# Diverter.net
KiCad netlist of a schematic drawn in Altium Designer
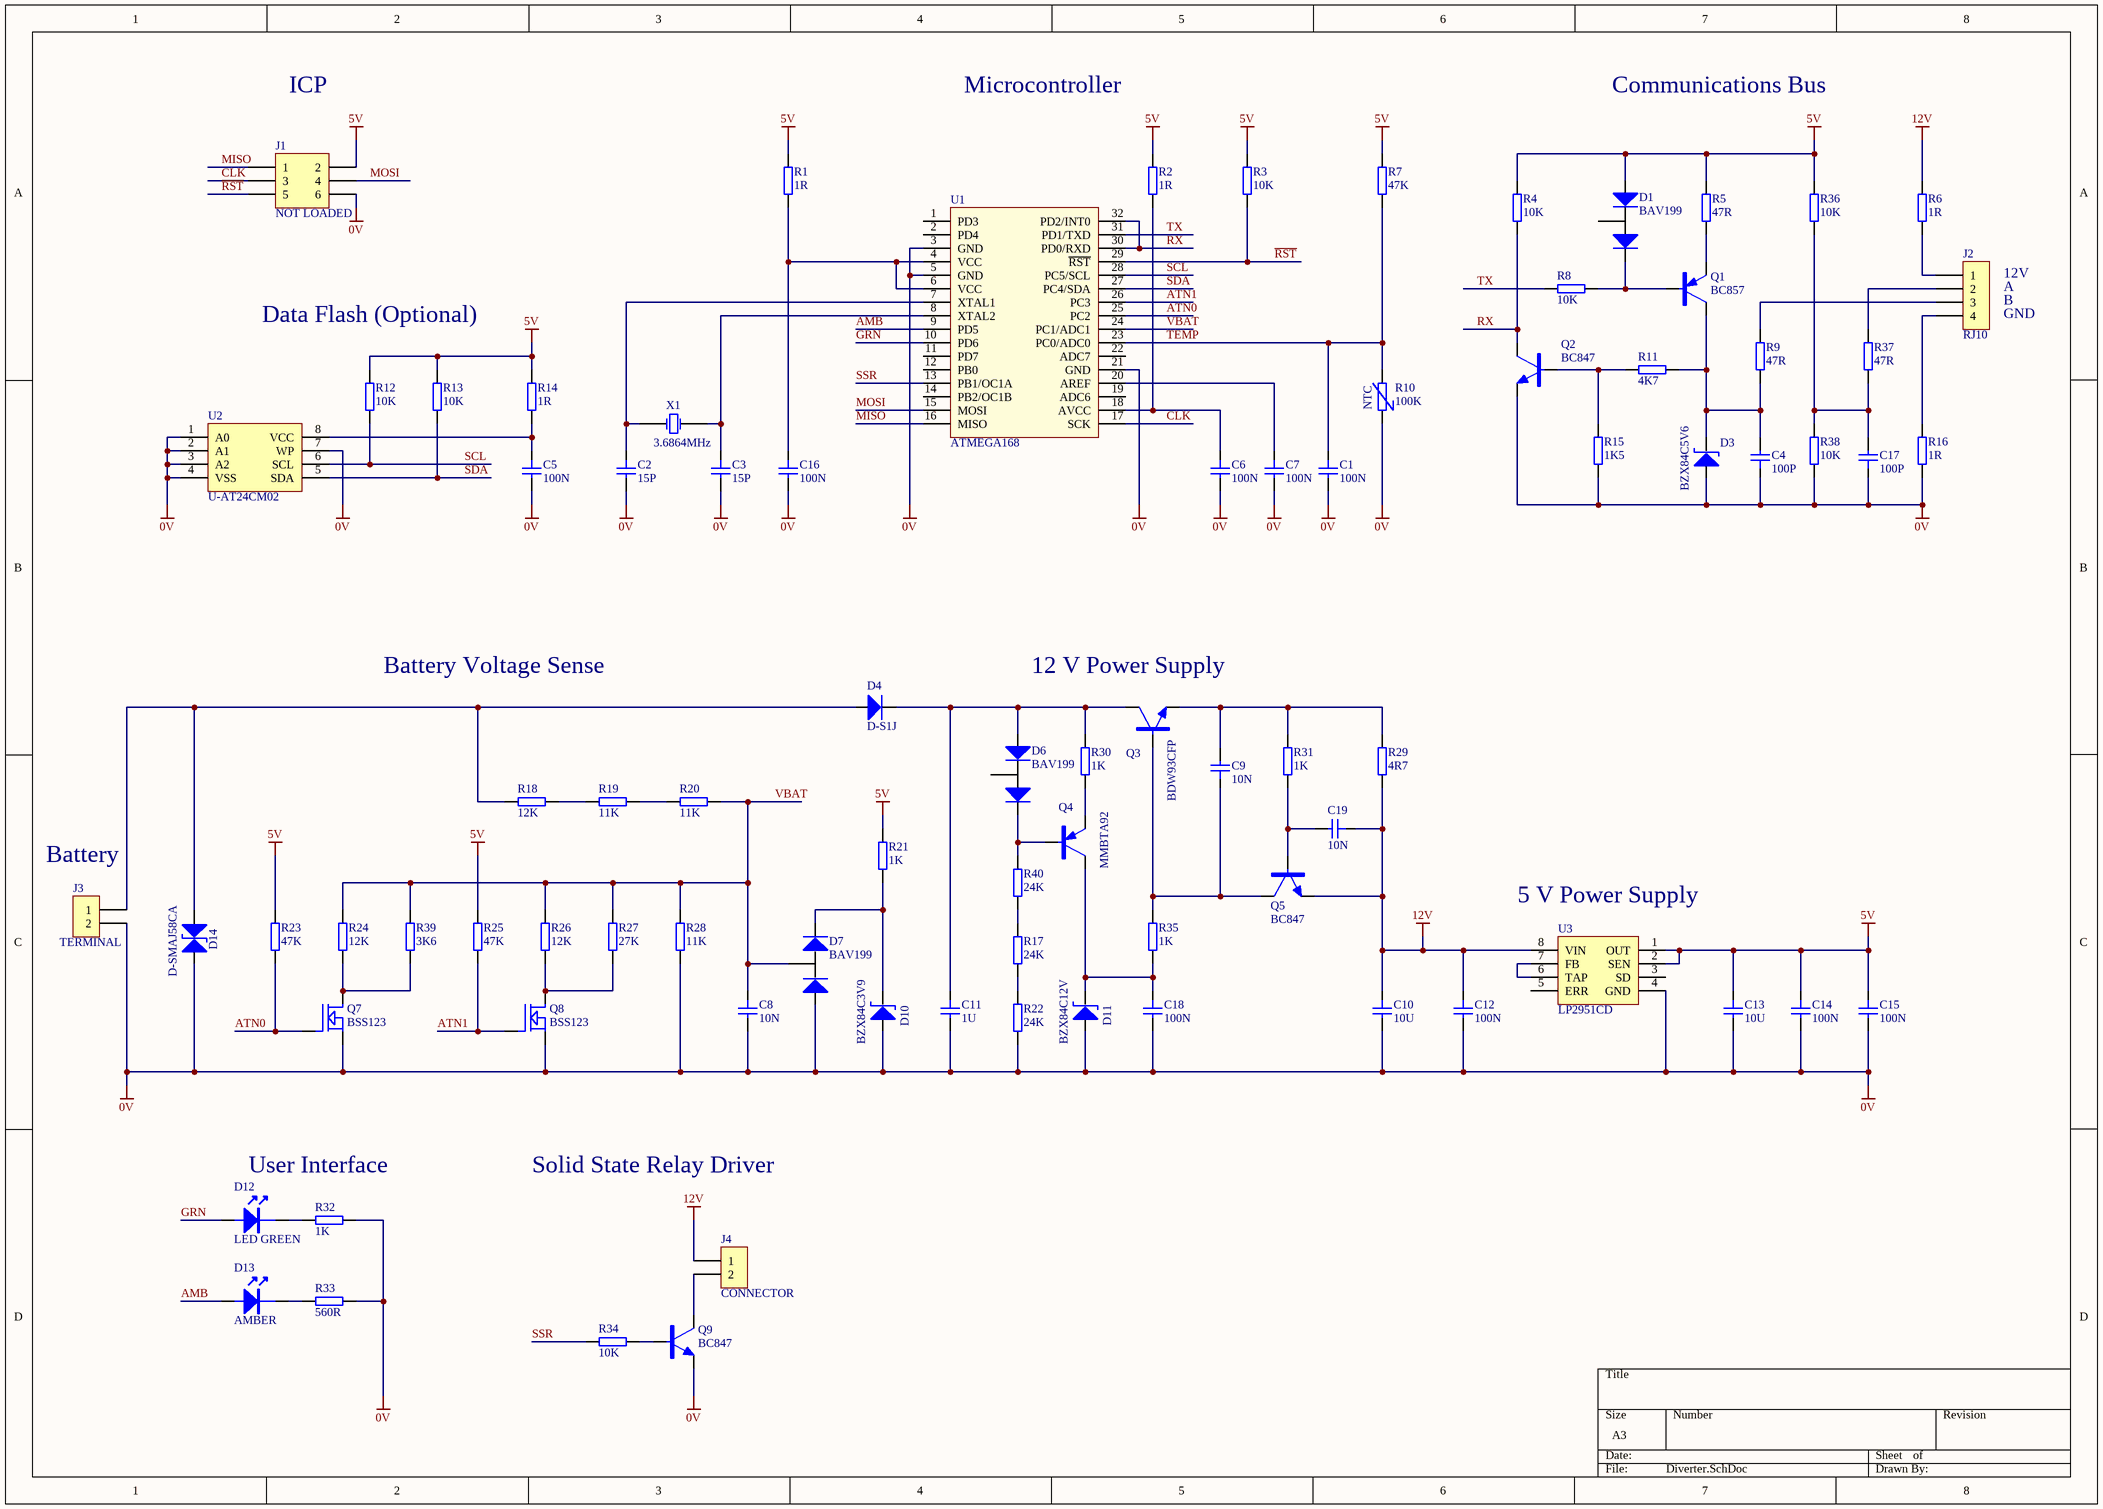
[diagram p0: Diverter.SchDoc]

(export (version "E")
  (design (tool "Eeschema 10.0.6"))
  (components
    (comp (ref "C1")
      (value "100N")
      (footprint "0805")
      (description "CAPACITOR")
      (libsource (lib "control") (part "C-B100N"))
    )
    (comp (ref "C2")
      (value "15P")
      (footprint "0805")
      (description "CAPACITOR")
      (libsource (lib "control") (part "C-B15P"))
    )
    (comp (ref "C3")
      (value "15P")
      (footprint "0805")
      (description "CAPACITOR")
      (libsource (lib "control") (part "C-B15P"))
    )
    (comp (ref "C4")
      (value "100P")
      (footprint "0805")
      (description "CAPACITOR")
      (libsource (lib "control") (part "C-B100P"))
    )
    (comp (ref "C5")
      (value "100N")
      (footprint "0805")
      (description "CAPACITOR")
      (libsource (lib "control") (part "C-B100N"))
    )
    (comp (ref "C6")
      (value "100N")
      (footprint "0805")
      (description "CAPACITOR")
      (libsource (lib "control") (part "C-B100N"))
    )
    (comp (ref "C7")
      (value "100N")
      (footprint "0805")
      (description "CAPACITOR")
      (libsource (lib "control") (part "C-B100N"))
    )
    (comp (ref "C8")
      (value "10N")
      (footprint "0805")
      (description "CAPACITOR")
      (libsource (lib "control") (part "C-B10N"))
    )
    (comp (ref "C9")
      (value "10N")
      (footprint "0805")
      (description "CAPACITOR")
      (libsource (lib "control") (part "C-B10N"))
    )
    (comp (ref "C10")
      (value "10U")
      (footprint "1206")
      (description "CAPACITOR")
      (libsource (lib "control") (part "C-C10U"))
    )
    (comp (ref "C11")
      (value "1U")
      (footprint "1206")
      (description "CAPACITOR")
      (libsource (lib "control") (part "C-D1U"))
    )
    (comp (ref "C12")
      (value "100N")
      (footprint "0805")
      (description "CAPACITOR")
      (libsource (lib "control") (part "C-B100N"))
    )
    (comp (ref "C13")
      (value "10U")
      (footprint "1206")
      (description "CAPACITOR")
      (libsource (lib "control") (part "C-C10U"))
    )
    (comp (ref "C14")
      (value "100N")
      (footprint "0805")
      (description "CAPACITOR")
      (libsource (lib "control") (part "C-B100N"))
    )
    (comp (ref "C15")
      (value "100N")
      (footprint "0805")
      (description "CAPACITOR")
      (libsource (lib "control") (part "C-B100N"))
    )
    (comp (ref "C16")
      (value "100N")
      (footprint "0805")
      (description "CAPACITOR")
      (libsource (lib "control") (part "C-B100N"))
    )
    (comp (ref "C17")
      (value "100P")
      (footprint "0805")
      (description "CAPACITOR")
      (libsource (lib "control") (part "C-B100P"))
    )
    (comp (ref "C18")
      (value "100N")
      (footprint "0805")
      (description "CAPACITOR")
      (libsource (lib "control") (part "C-B100N"))
    )
    (comp (ref "C19")
      (value "10N")
      (footprint "0805")
      (description "CAPACITOR")
      (libsource (lib "control") (part "C-B10N"))
    )
    (comp (ref "D1")
      (value "BAV199")
      (footprint "SOT23")
      (description "DUAL DIODE")
      (libsource (lib "control") (part "D-BAV199"))
    )
    (comp (ref "D3")
      (value "BZX84C5V6")
      (footprint "SOT23")
      (description "ZENER DIODE")
      (libsource (lib "control") (part "D-BZX84C5V6"))
    )
    (comp (ref "D4")
      (value "D-S1J")
      (footprint "SMA")
      (description "DIODE")
      (libsource (lib "control") (part "D-S1J"))
    )
    (comp (ref "D6")
      (value "BAV199")
      (footprint "SOT23")
      (description "DUAL DIODE")
      (libsource (lib "control") (part "D-BAV199"))
    )
    (comp (ref "D7")
      (value "BAV199")
      (footprint "SOT23")
      (description "DUAL DIODE")
      (libsource (lib "control") (part "D-BAV199"))
    )
    (comp (ref "D10")
      (value "BZX84C3V9")
      (footprint "SOT23")
      (description "ZENER DIODE")
      (libsource (lib "control") (part "D-BZX84C3V9"))
    )
    (comp (ref "D11")
      (value "BZX84C12V")
      (footprint "SOT23")
      (description "ZENER DIODE")
      (libsource (lib "control") (part "D-BZX84C12V"))
    )
    (comp (ref "D12")
      (value "LED GREEN")
      (footprint "LED5MM")
      (description "LED")
      (libsource (lib "control") (part "O-GREEN"))
    )
    (comp (ref "D13")
      (value "AMBER")
      (footprint "LED5MM")
      (description "LED")
      (libsource (lib "control") (part "O-AMBER"))
    )
    (comp (ref "D14")
      (value "D-SMAJ58CA")
      (footprint "SMA")
      (description "ZENER DIODE")
      (libsource (lib "control") (part "D-SMAJ58CA"))
    )
    (comp (ref "J1")
      (value "NOT LOADED")
      (footprint "HDR3X2")
      (description "CONNECTOR")
      (libsource (lib "control") (part "J-HDR2X3"))
    )
    (comp (ref "J2")
      (value "RJ10")
      (footprint "MOLEX85513")
      (description "CONNECTOR")
      (libsource (lib "control") (part "J-RJ10"))
    )
    (comp (ref "J3")
      (value "TERMINAL")
      (footprint "CTB9308")
      (description "CONNECTOR")
      (libsource (lib "control") (part "J-CON2VRT"))
    )
    (comp (ref "J4") (value "CONNECTOR") (footprint "CON2RA") (libsource (lib "control") (part "J-SSR")))
    (comp (ref "Q1")
      (value "BC857")
      (footprint "SOT23")
      (description "TRANSISTOR PNP")
      (libsource (lib "control") (part "Q-BC857"))
    )
    (comp (ref "Q2")
      (value "BC847")
      (footprint "SOT23")
      (description "TRANSISTOR NPN")
      (libsource (lib "") (part "Q-BC847_1"))
    )
    (comp (ref "Q3")
      (value "BDW93CFP")
      (footprint "TO220F")
      (description "TRANSISTOR NPN")
      (libsource (lib "control") (part "Q-BDW93CFP"))
    )
    (comp (ref "Q4")
      (value "MMBTA92")
      (footprint "SOT23")
      (description "TRANSISTOR PNP")
      (libsource (lib "control") (part "Q-MMBTA92"))
    )
    (comp (ref "Q5")
      (value "BC847")
      (footprint "SOT23")
      (description "TRANSISTOR NPN")
      (libsource (lib "control") (part "Q-BC847"))
    )
    (comp (ref "Q7")
      (value "BSS123")
      (footprint "SOT23")
      (description "N CH MOSFET")
      (libsource (lib "control") (part "Q-BSS123"))
    )
    (comp (ref "Q8")
      (value "BSS123")
      (footprint "SOT23")
      (description "N CH MOSFET")
      (libsource (lib "control") (part "Q-BSS123"))
    )
    (comp (ref "Q9")
      (value "BC847")
      (footprint "SOT23")
      (description "TRANSISTOR NPN")
      (libsource (lib "") (part "Q-BC847_1"))
    )
    (comp (ref "R1")
      (value "1R")
      (footprint "0805")
      (description "RESISTOR")
      (libsource (lib "control") (part "R-B1R"))
    )
    (comp (ref "R2")
      (value "1R")
      (footprint "0805")
      (description "RESISTOR")
      (libsource (lib "control") (part "R-B1R"))
    )
    (comp (ref "R3")
      (value "10K")
      (footprint "0805")
      (description "RESISTOR")
      (libsource (lib "control") (part "R-B10K"))
    )
    (comp (ref "R4")
      (value "10K")
      (footprint "0805")
      (description "RESISTOR")
      (libsource (lib "control") (part "R-B10K"))
    )
    (comp (ref "R5")
      (value "47R")
      (footprint "0805")
      (description "RESISTOR")
      (libsource (lib "control") (part "R-B47R"))
    )
    (comp (ref "R6")
      (value "1R")
      (footprint "0805")
      (description "RESISTOR")
      (libsource (lib "control") (part "R-B1R"))
    )
    (comp (ref "R7")
      (value "47K")
      (footprint "0805")
      (description "RESISTOR")
      (libsource (lib "control") (part "R-B47K"))
    )
    (comp (ref "R8")
      (value "10K")
      (footprint "0805")
      (description "RESISTOR")
      (libsource (lib "control") (part "R-B10K"))
    )
    (comp (ref "R9")
      (value "47R")
      (footprint "0805")
      (description "RESISTOR")
      (libsource (lib "control") (part "R-B47R"))
    )
    (comp (ref "R10")
      (value "100K")
      (footprint "0805")
      (description "THERMISTOR")
      (libsource (lib "control") (part "R-NTC100K"))
    )
    (comp (ref "R11")
      (value "4K7")
      (footprint "0805")
      (description "RESISTOR")
      (libsource (lib "control") (part "R-B4K7"))
    )
    (comp (ref "R12")
      (value "10K")
      (footprint "0805")
      (description "RESISTOR")
      (libsource (lib "control") (part "R-B10K"))
    )
    (comp (ref "R13")
      (value "10K")
      (footprint "0805")
      (description "RESISTOR")
      (libsource (lib "control") (part "R-B10K"))
    )
    (comp (ref "R14")
      (value "1R")
      (footprint "0805")
      (description "RESISTOR")
      (libsource (lib "control") (part "R-B1R"))
    )
    (comp (ref "R15")
      (value "1K5")
      (footprint "0805")
      (description "RESISTOR")
      (libsource (lib "control") (part "R-B1K5"))
    )
    (comp (ref "R16")
      (value "1R")
      (footprint "0805")
      (description "RESISTOR")
      (libsource (lib "control") (part "R-B1R"))
    )
    (comp (ref "R17")
      (value "24K")
      (footprint "1206")
      (description "RESISTOR")
      (libsource (lib "control") (part "R-C24K"))
    )
    (comp (ref "R18")
      (value "12K")
      (footprint "1206")
      (description "RESISTOR")
      (libsource (lib "control") (part "R-C12K"))
    )
    (comp (ref "R19")
      (value "11K")
      (footprint "1206")
      (description "RESISTOR")
      (libsource (lib "control") (part "R-C11K"))
    )
    (comp (ref "R20")
      (value "11K")
      (footprint "1206")
      (description "RESISTOR")
      (libsource (lib "control") (part "R-C11K"))
    )
    (comp (ref "R21")
      (value "1K")
      (footprint "0805")
      (description "RESISTOR")
      (libsource (lib "control") (part "R-B1K"))
    )
    (comp (ref "R22")
      (value "24K")
      (footprint "1206")
      (description "RESISTOR")
      (libsource (lib "control") (part "R-C24K"))
    )
    (comp (ref "R23")
      (value "47K")
      (footprint "0805")
      (description "RESISTOR")
      (libsource (lib "control") (part "R-B47K"))
    )
    (comp (ref "R24")
      (value "12K")
      (footprint "0805")
      (description "RESISTOR")
      (libsource (lib "control") (part "R-B12K"))
    )
    (comp (ref "R25")
      (value "47K")
      (footprint "0805")
      (description "RESISTOR")
      (libsource (lib "control") (part "R-B47K"))
    )
    (comp (ref "R26")
      (value "12K")
      (footprint "0805")
      (description "RESISTOR")
      (libsource (lib "control") (part "R-B12K"))
    )
    (comp (ref "R27")
      (value "27K")
      (footprint "0805")
      (description "RESISTOR")
      (libsource (lib "control") (part "R-B27K"))
    )
    (comp (ref "R28")
      (value "11K")
      (footprint "1206")
      (description "RESISTOR")
      (libsource (lib "control") (part "R-C11K"))
    )
    (comp (ref "R29")
      (value "4R7")
      (footprint "1206")
      (description "RESISTOR")
      (libsource (lib "control") (part "R-C4R7"))
    )
    (comp (ref "R30")
      (value "1K")
      (footprint "0805")
      (description "RESISTOR")
      (libsource (lib "control") (part "R-B1K"))
    )
    (comp (ref "R31")
      (value "1K")
      (footprint "0805")
      (description "RESISTOR")
      (libsource (lib "control") (part "R-B1K"))
    )
    (comp (ref "R32")
      (value "1K")
      (footprint "0805")
      (description "RESISTOR")
      (libsource (lib "control") (part "R-B1K"))
    )
    (comp (ref "R33")
      (value "560R")
      (footprint "0805")
      (description "RESISTOR")
      (libsource (lib "control") (part "R-B560R"))
    )
    (comp (ref "R34")
      (value "10K")
      (footprint "0805")
      (description "RESISTOR")
      (libsource (lib "control") (part "R-B10K"))
    )
    (comp (ref "R35")
      (value "1K")
      (footprint "0805")
      (description "RESISTOR")
      (libsource (lib "control") (part "R-B1K"))
    )
    (comp (ref "R36")
      (value "10K")
      (footprint "0805")
      (description "RESISTOR")
      (libsource (lib "control") (part "R-B10K"))
    )
    (comp (ref "R37")
      (value "47R")
      (footprint "0805")
      (description "RESISTOR")
      (libsource (lib "control") (part "R-B47R"))
    )
    (comp (ref "R38")
      (value "10K")
      (footprint "0805")
      (description "RESISTOR")
      (libsource (lib "control") (part "R-B10K"))
    )
    (comp (ref "R39")
      (value "3K6")
      (footprint "0805")
      (description "RESISTOR")
      (libsource (lib "control") (part "R-B3K6"))
    )
    (comp (ref "R40")
      (value "24K")
      (footprint "1206")
      (description "RESISTOR")
      (libsource (lib "control") (part "R-C24K"))
    )
    (comp (ref "U1")
      (value "ATMEGA168")
      (footprint "TQFP32")
      (description "MICROCONTROLLER")
      (libsource (lib "control") (part "U-ATMEGA168"))
    )
    (comp (ref "U2")
      (value "U-AT24CM02")
      (footprint "SO8")
      (description "I2C 2MBIT EEPROM")
      (libsource (lib "control") (part "U-AT24CM02-SSHD-B"))
    )
    (comp (ref "U3")
      (value "LP2951CD")
      (footprint "SO8")
      (description "VOLTAGE REGULATOR 5V")
      (libsource (lib "control") (part "U-LP2951CD"))
    )
    (comp (ref "X1")
      (value "3.6864MHz")
      (footprint "HC49")
      (description "CRYSTAL")
      (libsource (lib "control") (part "X-3M6864"))
    )
  )
  (nets
    (net (code "1") (name "/AMB") (class "Default")
      (node (ref "D13") (pin "1") (pinfunction "A_1") (pintype "passive"))
      (node (ref "U1") (pin "9") (pinfunction "PD5_9") (pintype "passive"))
    )
    (net (code "2") (name "/ATN0") (class "Default")
      (node (ref "Q7") (pin "1") (pinfunction "G_1") (pintype "passive"))
      (node (ref "R23") (pin "1") (pinfunction "1_1") (pintype "passive"))
      (node (ref "U1") (pin "25") (pinfunction "PC2_25") (pintype "passive"))
    )
    (net (code "3") (name "/ATN1") (class "Default")
      (node (ref "Q8") (pin "1") (pinfunction "G_1") (pintype "passive"))
      (node (ref "R25") (pin "1") (pinfunction "1_1") (pintype "passive"))
      (node (ref "U1") (pin "26") (pinfunction "PC3_26") (pintype "passive"))
    )
    (net (code "4") (name "/CLK") (class "Default")
      (node (ref "J1") (pin "3") (pinfunction "3_3") (pintype "passive"))
      (node (ref "U1") (pin "17") (pinfunction "SCK_17") (pintype "passive"))
    )
    (net (code "5") (name "/GRN") (class "Default")
      (node (ref "D12") (pin "1") (pinfunction "A_1") (pintype "passive"))
      (node (ref "U1") (pin "10") (pinfunction "PD6_10") (pintype "passive"))
    )
    (net (code "6") (name "/MISO") (class "Default")
      (node (ref "J1") (pin "1") (pinfunction "1_1") (pintype "passive"))
      (node (ref "U1") (pin "16") (pinfunction "MISO_16") (pintype "passive"))
    )
    (net (code "7") (name "/MOSI") (class "Default")
      (node (ref "J1") (pin "4") (pinfunction "4_4") (pintype "passive"))
      (node (ref "U1") (pin "15") (pinfunction "MOSI_15") (pintype "passive"))
    )
    (net (code "8") (name "/RX") (class "Default")
      (node (ref "Q2") (pin "3") (pinfunction "C_3") (pintype "passive"))
      (node (ref "R4") (pin "1") (pinfunction "1_1") (pintype "passive"))
      (node (ref "U1") (pin "30") (pinfunction "PD0/RXD_30") (pintype "passive"))
      (node (ref "U1") (pin "32") (pinfunction "PD2/INT0_32") (pintype "passive"))
    )
    (net (code "9") (name "/SCL") (class "Default")
      (node (ref "R12") (pin "1") (pinfunction "1_1") (pintype "passive"))
      (node (ref "U1") (pin "28") (pinfunction "PC5/SCL_28") (pintype "passive"))
      (node (ref "U2") (pin "6") (pinfunction "SCL_6") (pintype "passive"))
    )
    (net (code "10") (name "/SDA") (class "Default")
      (node (ref "R13") (pin "1") (pinfunction "1_1") (pintype "passive"))
      (node (ref "U1") (pin "27") (pinfunction "PC4/SDA_27") (pintype "passive"))
      (node (ref "U2") (pin "5") (pinfunction "SDA_5") (pintype "passive"))
    )
    (net (code "11") (name "/SSR") (class "Default")
      (node (ref "R34") (pin "2") (pinfunction "2_2") (pintype "passive"))
      (node (ref "U1") (pin "13") (pinfunction "PB1/OC1A_13") (pintype "passive"))
    )
    (net (code "12") (name "/TEMP") (class "Default")
      (node (ref "C1") (pin "2") (pinfunction "2_2") (pintype "passive"))
      (node (ref "R10") (pin "2") (pinfunction "2_2") (pintype "passive"))
      (node (ref "R7") (pin "1") (pinfunction "1_1") (pintype "passive"))
      (node (ref "U1") (pin "23") (pinfunction "PC0/ADC0_23") (pintype "passive"))
    )
    (net (code "13") (name "/TX") (class "Default")
      (node (ref "R8") (pin "2") (pinfunction "2_2") (pintype "passive"))
      (node (ref "U1") (pin "31") (pinfunction "PD1/TXD_31") (pintype "passive"))
    )
    (net (code "14") (name "/VBAT") (class "Default")
      (node (ref "C8") (pin "2") (pinfunction "2_2") (pintype "passive"))
      (node (ref "D7") (pin "3") (pinfunction "C_3") (pintype "passive"))
      (node (ref "R20") (pin "1") (pinfunction "1_1") (pintype "passive"))
      (node (ref "R24") (pin "2") (pinfunction "2_2") (pintype "passive"))
      (node (ref "R26") (pin "2") (pinfunction "2_2") (pintype "passive"))
      (node (ref "R27") (pin "2") (pinfunction "2_2") (pintype "passive"))
      (node (ref "R28") (pin "2") (pinfunction "2_2") (pintype "passive"))
      (node (ref "R39") (pin "2") (pinfunction "2_2") (pintype "passive"))
      (node (ref "U1") (pin "24") (pinfunction "PC1/ADC1_24") (pintype "passive"))
    )
    (net (code "15") (name "/~{RST}") (class "Default")
      (node (ref "J1") (pin "5") (pinfunction "5_5") (pintype "passive"))
      (node (ref "R3") (pin "1") (pinfunction "1_1") (pintype "passive"))
      (node (ref "U1") (pin "29") (pinfunction "~{RST}_29") (pintype "passive"))
    )
    (net (code "16") (name "0V") (class "Default")
      (node (ref "C1") (pin "1") (pinfunction "1_1") (pintype "passive"))
      (node (ref "C10") (pin "1") (pinfunction "1_1") (pintype "passive"))
      (node (ref "C11") (pin "1") (pinfunction "1_1") (pintype "passive"))
      (node (ref "C12") (pin "1") (pinfunction "1_1") (pintype "passive"))
      (node (ref "C13") (pin "1") (pinfunction "1_1") (pintype "passive"))
      (node (ref "C14") (pin "1") (pinfunction "1_1") (pintype "passive"))
      (node (ref "C15") (pin "1") (pinfunction "1_1") (pintype "passive"))
      (node (ref "C16") (pin "1") (pinfunction "1_1") (pintype "passive"))
      (node (ref "C17") (pin "2") (pinfunction "2_2") (pintype "passive"))
      (node (ref "C18") (pin "1") (pinfunction "1_1") (pintype "passive"))
      (node (ref "C2") (pin "1") (pinfunction "1_1") (pintype "passive"))
      (node (ref "C3") (pin "1") (pinfunction "1_1") (pintype "passive"))
      (node (ref "C4") (pin "2") (pinfunction "2_2") (pintype "passive"))
      (node (ref "C5") (pin "1") (pinfunction "1_1") (pintype "passive"))
      (node (ref "C6") (pin "1") (pinfunction "1_1") (pintype "passive"))
      (node (ref "C7") (pin "1") (pinfunction "1_1") (pintype "passive"))
      (node (ref "C8") (pin "1") (pinfunction "1_1") (pintype "passive"))
      (node (ref "D10") (pin "1") (pinfunction "A_1") (pintype "passive"))
      (node (ref "D11") (pin "1") (pinfunction "A_1") (pintype "passive"))
      (node (ref "D14") (pin "1") (pinfunction "A_1") (pintype "passive"))
      (node (ref "D3") (pin "1") (pinfunction "A_1") (pintype "passive"))
      (node (ref "D7") (pin "1") (pinfunction "A_1") (pintype "passive"))
      (node (ref "J1") (pin "6") (pinfunction "6_6") (pintype "passive"))
      (node (ref "J3") (pin "2") (pinfunction "2_2") (pintype "passive"))
      (node (ref "Q2") (pin "2") (pinfunction "E_2") (pintype "passive"))
      (node (ref "Q7") (pin "2") (pinfunction "S_2") (pintype "passive"))
      (node (ref "Q8") (pin "2") (pinfunction "S_2") (pintype "passive"))
      (node (ref "Q9") (pin "2") (pinfunction "E_2") (pintype "passive"))
      (node (ref "R10") (pin "1") (pinfunction "1_1") (pintype "passive"))
      (node (ref "R15") (pin "1") (pinfunction "1_1") (pintype "passive"))
      (node (ref "R16") (pin "1") (pinfunction "1_1") (pintype "passive"))
      (node (ref "R22") (pin "2") (pinfunction "2_2") (pintype "passive"))
      (node (ref "R28") (pin "1") (pinfunction "1_1") (pintype "passive"))
      (node (ref "R32") (pin "2") (pinfunction "2_2") (pintype "passive"))
      (node (ref "R33") (pin "2") (pinfunction "2_2") (pintype "passive"))
      (node (ref "R38") (pin "1") (pinfunction "1_1") (pintype "passive"))
      (node (ref "U1") (pin "21") (pinfunction "GND_21") (pintype "passive"))
      (node (ref "U1") (pin "3") (pinfunction "GND_3") (pintype "passive"))
      (node (ref "U1") (pin "5") (pinfunction "GND_5") (pintype "passive"))
      (node (ref "U2") (pin "1") (pinfunction "A0_1") (pintype "passive"))
      (node (ref "U2") (pin "2") (pinfunction "A1_2") (pintype "passive"))
      (node (ref "U2") (pin "3") (pinfunction "A2_3") (pintype "passive"))
      (node (ref "U2") (pin "4") (pinfunction "VSS_4") (pintype "passive"))
      (node (ref "U2") (pin "7") (pinfunction "WP_7") (pintype "passive"))
      (node (ref "U3") (pin "4") (pinfunction "GND_4") (pintype "passive"))
    )
    (net (code "17") (name "5V") (class "Default")
      (node (ref "C13") (pin "2") (pinfunction "2_2") (pintype "passive"))
      (node (ref "C14") (pin "2") (pinfunction "2_2") (pintype "passive"))
      (node (ref "C15") (pin "2") (pinfunction "2_2") (pintype "passive"))
      (node (ref "D1") (pin "1") (pinfunction "A_1") (pintype "passive"))
      (node (ref "J1") (pin "2") (pinfunction "2_2") (pintype "passive"))
      (node (ref "R1") (pin "2") (pinfunction "2_2") (pintype "passive"))
      (node (ref "R12") (pin "2") (pinfunction "2_2") (pintype "passive"))
      (node (ref "R13") (pin "2") (pinfunction "2_2") (pintype "passive"))
      (node (ref "R14") (pin "2") (pinfunction "2_2") (pintype "passive"))
      (node (ref "R2") (pin "2") (pinfunction "2_2") (pintype "passive"))
      (node (ref "R21") (pin "2") (pinfunction "2_2") (pintype "passive"))
      (node (ref "R23") (pin "2") (pinfunction "2_2") (pintype "passive"))
      (node (ref "R25") (pin "2") (pinfunction "2_2") (pintype "passive"))
      (node (ref "R3") (pin "2") (pinfunction "2_2") (pintype "passive"))
      (node (ref "R36") (pin "2") (pinfunction "2_2") (pintype "passive"))
      (node (ref "R4") (pin "2") (pinfunction "2_2") (pintype "passive"))
      (node (ref "R5") (pin "2") (pinfunction "2_2") (pintype "passive"))
      (node (ref "R7") (pin "2") (pinfunction "2_2") (pintype "passive"))
      (node (ref "U3") (pin "1") (pinfunction "OUT_1") (pintype "passive"))
      (node (ref "U3") (pin "2") (pinfunction "SEN_2") (pintype "passive"))
    )
    (net (code "18") (name "12V") (class "Default")
      (node (ref "C10") (pin "2") (pinfunction "2_2") (pintype "passive"))
      (node (ref "C12") (pin "2") (pinfunction "2_2") (pintype "passive"))
      (node (ref "C19") (pin "2") (pinfunction "2_2") (pintype "passive"))
      (node (ref "J4") (pin "1") (pinfunction "1_1") (pintype "passive"))
      (node (ref "Q5") (pin "2") (pinfunction "E_2") (pintype "passive"))
      (node (ref "R29") (pin "2") (pinfunction "2_2") (pintype "passive"))
      (node (ref "R6") (pin "2") (pinfunction "2_2") (pintype "passive"))
      (node (ref "U3") (pin "8") (pinfunction "VIN_8") (pintype "passive"))
    )
    (net (code "19") (name "Net-(C16-Pad2)") (class "Default")
      (node (ref "C16") (pin "2") (pinfunction "2_2") (pintype "passive"))
      (node (ref "R1") (pin "1") (pinfunction "1_1") (pintype "passive"))
      (node (ref "U1") (pin "4") (pinfunction "VCC_4") (pintype "passive"))
      (node (ref "U1") (pin "6") (pinfunction "VCC_6") (pintype "passive"))
    )
    (net (code "20") (name "Net-(C17-Pad1)") (class "Default")
      (node (ref "C17") (pin "1") (pinfunction "1_1") (pintype "passive"))
      (node (ref "R36") (pin "1") (pinfunction "1_1") (pintype "passive"))
      (node (ref "R37") (pin "1") (pinfunction "1_1") (pintype "passive"))
      (node (ref "R38") (pin "2") (pinfunction "2_2") (pintype "passive"))
    )
    (net (code "21") (name "Net-(D1-K)") (class "Default")
      (node (ref "D1") (pin "2") (pinfunction "K_2") (pintype "passive"))
      (node (ref "Q1") (pin "1") (pinfunction "B_1") (pintype "passive"))
      (node (ref "R8") (pin "1") (pinfunction "1_1") (pintype "passive"))
    )
    (net (code "22") (name "Net-(D3-K)") (class "Default")
      (node (ref "C4") (pin "1") (pinfunction "1_1") (pintype "passive"))
      (node (ref "D3") (pin "3") (pinfunction "K_3") (pintype "passive"))
      (node (ref "Q1") (pin "3") (pinfunction "C_3") (pintype "passive"))
      (node (ref "R11") (pin "2") (pinfunction "2_2") (pintype "passive"))
      (node (ref "R9") (pin "1") (pinfunction "1_1") (pintype "passive"))
    )
    (net (code "23") (name "Net-(D4-K)") (class "Default")
      (node (ref "C11") (pin "2") (pinfunction "2_2") (pintype "passive"))
      (node (ref "D4") (pin "2") (pinfunction "K_2") (pintype "passive"))
      (node (ref "D6") (pin "1") (pinfunction "A_1") (pintype "passive"))
      (node (ref "Q3") (pin "2") (pinfunction "C_2") (pintype "passive"))
      (node (ref "R30") (pin "2") (pinfunction "2_2") (pintype "passive"))
    )
    (net (code "24") (name "Net-(D6-K)") (class "Default")
      (node (ref "D6") (pin "2") (pinfunction "K_2") (pintype "passive"))
      (node (ref "Q4") (pin "1") (pinfunction "B_1") (pintype "passive"))
      (node (ref "R40") (pin "1") (pinfunction "1_1") (pintype "passive"))
    )
    (net (code "25") (name "Net-(D10-K)") (class "Default")
      (node (ref "D10") (pin "3") (pinfunction "K_3") (pintype "passive"))
      (node (ref "D7") (pin "2") (pinfunction "K_2") (pintype "passive"))
      (node (ref "R21") (pin "1") (pinfunction "1_1") (pintype "passive"))
    )
    (net (code "26") (name "Net-(D11-K)") (class "Default")
      (node (ref "C18") (pin "2") (pinfunction "2_2") (pintype "passive"))
      (node (ref "D11") (pin "3") (pinfunction "K_3") (pintype "passive"))
      (node (ref "Q4") (pin "3") (pinfunction "C_3") (pintype "passive"))
      (node (ref "R35") (pin "2") (pinfunction "2_2") (pintype "passive"))
    )
    (net (code "27") (name "Net-(D12-K)") (class "Default")
      (node (ref "D12") (pin "2") (pinfunction "K_2") (pintype "passive"))
      (node (ref "R32") (pin "1") (pinfunction "1_1") (pintype "passive"))
    )
    (net (code "28") (name "Net-(D13-K)") (class "Default")
      (node (ref "D13") (pin "2") (pinfunction "K_2") (pintype "passive"))
      (node (ref "R33") (pin "1") (pinfunction "1_1") (pintype "passive"))
    )
    (net (code "29") (name "Net-(D14-K)") (class "Default")
      (node (ref "D14") (pin "2") (pinfunction "K_2") (pintype "passive"))
      (node (ref "D4") (pin "1") (pinfunction "A_1") (pintype "passive"))
      (node (ref "J3") (pin "1") (pinfunction "1_1") (pintype "passive"))
      (node (ref "R18") (pin "1") (pinfunction "1_1") (pintype "passive"))
    )
    (net (code "30") (name "Net-(J2-Pad1)") (class "Default")
      (node (ref "J2") (pin "1") (pinfunction "1_1") (pintype "passive"))
      (node (ref "R6") (pin "1") (pinfunction "1_1") (pintype "passive"))
    )
    (net (code "31") (name "Net-(J2-Pad2)") (class "Default")
      (node (ref "J2") (pin "2") (pinfunction "2_2") (pintype "passive"))
      (node (ref "R37") (pin "2") (pinfunction "2_2") (pintype "passive"))
    )
    (net (code "32") (name "Net-(J2-Pad3)") (class "Default")
      (node (ref "J2") (pin "3") (pinfunction "3_3") (pintype "passive"))
      (node (ref "R9") (pin "2") (pinfunction "2_2") (pintype "passive"))
    )
    (net (code "33") (name "Net-(J2-Pad4)") (class "Default")
      (node (ref "J2") (pin "4") (pinfunction "4_4") (pintype "passive"))
      (node (ref "R16") (pin "2") (pinfunction "2_2") (pintype "passive"))
    )
    (net (code "34") (name "Net-(Q1-E)") (class "Default")
      (node (ref "Q1") (pin "2") (pinfunction "E_2") (pintype "passive"))
      (node (ref "R5") (pin "1") (pinfunction "1_1") (pintype "passive"))
    )
    (net (code "35") (name "Net-(Q2-B)") (class "Default")
      (node (ref "Q2") (pin "1") (pinfunction "B_1") (pintype "passive"))
      (node (ref "R11") (pin "1") (pinfunction "1_1") (pintype "passive"))
      (node (ref "R15") (pin "2") (pinfunction "2_2") (pintype "passive"))
    )
    (net (code "36") (name "Net-(Q3-B)") (class "Default")
      (node (ref "C9") (pin "2") (pinfunction "2_2") (pintype "passive"))
      (node (ref "Q3") (pin "1") (pinfunction "B_1") (pintype "passive"))
      (node (ref "Q5") (pin "3") (pinfunction "C_3") (pintype "passive"))
      (node (ref "R35") (pin "1") (pinfunction "1_1") (pintype "passive"))
    )
    (net (code "37") (name "Net-(Q3-E)") (class "Default")
      (node (ref "C9") (pin "1") (pinfunction "1_1") (pintype "passive"))
      (node (ref "Q3") (pin "3") (pinfunction "E_3") (pintype "passive"))
      (node (ref "R29") (pin "1") (pinfunction "1_1") (pintype "passive"))
      (node (ref "R31") (pin "2") (pinfunction "2_2") (pintype "passive"))
    )
    (net (code "38") (name "Net-(Q4-E)") (class "Default")
      (node (ref "Q4") (pin "2") (pinfunction "E_2") (pintype "passive"))
      (node (ref "R30") (pin "1") (pinfunction "1_1") (pintype "passive"))
    )
    (net (code "39") (name "Net-(Q5-B)") (class "Default")
      (node (ref "C19") (pin "1") (pinfunction "1_1") (pintype "passive"))
      (node (ref "Q5") (pin "1") (pinfunction "B_1") (pintype "passive"))
      (node (ref "R31") (pin "1") (pinfunction "1_1") (pintype "passive"))
    )
    (net (code "40") (name "Net-(Q7-D)") (class "Default")
      (node (ref "Q7") (pin "3") (pinfunction "D_3") (pintype "passive"))
      (node (ref "R24") (pin "1") (pinfunction "1_1") (pintype "passive"))
      (node (ref "R39") (pin "1") (pinfunction "1_1") (pintype "passive"))
    )
    (net (code "41") (name "Net-(Q8-D)") (class "Default")
      (node (ref "Q8") (pin "3") (pinfunction "D_3") (pintype "passive"))
      (node (ref "R26") (pin "1") (pinfunction "1_1") (pintype "passive"))
      (node (ref "R27") (pin "1") (pinfunction "1_1") (pintype "passive"))
    )
    (net (code "42") (name "Net-(Q9-B)") (class "Default")
      (node (ref "Q9") (pin "1") (pinfunction "B_1") (pintype "passive"))
      (node (ref "R34") (pin "1") (pinfunction "1_1") (pintype "passive"))
    )
    (net (code "43") (name "Net-(Q9-C)") (class "Default")
      (node (ref "J4") (pin "2") (pinfunction "2_2") (pintype "passive"))
      (node (ref "Q9") (pin "3") (pinfunction "C_3") (pintype "passive"))
    )
    (net (code "44") (name "Net-(R17-Pad1)") (class "Default")
      (node (ref "R17") (pin "1") (pinfunction "1_1") (pintype "passive"))
      (node (ref "R40") (pin "2") (pinfunction "2_2") (pintype "passive"))
    )
    (net (code "45") (name "Net-(R17-Pad2)") (class "Default")
      (node (ref "R17") (pin "2") (pinfunction "2_2") (pintype "passive"))
      (node (ref "R22") (pin "1") (pinfunction "1_1") (pintype "passive"))
    )
    (net (code "46") (name "Net-(R18-Pad2)") (class "Default")
      (node (ref "R18") (pin "2") (pinfunction "2_2") (pintype "passive"))
      (node (ref "R19") (pin "2") (pinfunction "2_2") (pintype "passive"))
    )
    (net (code "47") (name "Net-(R19-Pad1)") (class "Default")
      (node (ref "R19") (pin "1") (pinfunction "1_1") (pintype "passive"))
      (node (ref "R20") (pin "2") (pinfunction "2_2") (pintype "passive"))
    )
    (net (code "48") (name "Net-(U1-AREF)") (class "Default")
      (node (ref "C7") (pin "2") (pinfunction "2_2") (pintype "passive"))
      (node (ref "U1") (pin "20") (pinfunction "AREF_20") (pintype "passive"))
    )
    (net (code "49") (name "Net-(U1-AVCC)") (class "Default")
      (node (ref "C6") (pin "2") (pinfunction "2_2") (pintype "passive"))
      (node (ref "R2") (pin "1") (pinfunction "1_1") (pintype "passive"))
      (node (ref "U1") (pin "18") (pinfunction "AVCC_18") (pintype "passive"))
    )
    (net (code "50") (name "Net-(U1-XTAL1)") (class "Default")
      (node (ref "C2") (pin "2") (pinfunction "2_2") (pintype "passive"))
      (node (ref "U1") (pin "7") (pinfunction "XTAL1_7") (pintype "passive"))
      (node (ref "X1") (pin "1") (pinfunction "OSC1_1") (pintype "passive"))
    )
    (net (code "51") (name "Net-(U1-XTAL2)") (class "Default")
      (node (ref "C3") (pin "2") (pinfunction "2_2") (pintype "passive"))
      (node (ref "U1") (pin "8") (pinfunction "XTAL2_8") (pintype "passive"))
      (node (ref "X1") (pin "2") (pinfunction "OSC2_2") (pintype "passive"))
    )
    (net (code "52") (name "Net-(U2-VCC)") (class "Default")
      (node (ref "C5") (pin "2") (pinfunction "2_2") (pintype "passive"))
      (node (ref "R14") (pin "1") (pinfunction "1_1") (pintype "passive"))
      (node (ref "U2") (pin "8") (pinfunction "VCC_8") (pintype "passive"))
    )
    (net (code "53") (name "Net-(U3-FB)") (class "Default")
      (node (ref "U3") (pin "6") (pinfunction "TAP_6") (pintype "passive"))
      (node (ref "U3") (pin "7") (pinfunction "FB_7") (pintype "passive"))
    )
    (net (code "54") (name "unconnected-(D1-C-Pad3)") (class "Default")
      (node (ref "D1") (pin "3") (pinfunction "C_3") (pintype "passive"))
    )
    (net (code "55") (name "unconnected-(D6-C-Pad3)") (class "Default")
      (node (ref "D6") (pin "3") (pinfunction "C_3") (pintype "passive"))
    )
    (net (code "56") (name "unconnected-(U1-ADC6-Pad19)") (class "Default")
      (node (ref "U1") (pin "19") (pinfunction "ADC6_19") (pintype "passive"))
    )
    (net (code "57") (name "unconnected-(U1-ADC7-Pad22)") (class "Default")
      (node (ref "U1") (pin "22") (pinfunction "ADC7_22") (pintype "passive"))
    )
    (net (code "58") (name "unconnected-(U1-PB0-Pad12)") (class "Default")
      (node (ref "U1") (pin "12") (pinfunction "PB0_12") (pintype "passive"))
    )
    (net (code "59") (name "unconnected-(U1-PB2{slash}OC1B-Pad14)") (class "Default")
      (node (ref "U1") (pin "14") (pinfunction "PB2/OC1B_14") (pintype "passive"))
    )
    (net (code "60") (name "unconnected-(U1-PD3-Pad1)") (class "Default")
      (node (ref "U1") (pin "1") (pinfunction "PD3_1") (pintype "passive"))
    )
    (net (code "61") (name "unconnected-(U1-PD4-Pad2)") (class "Default")
      (node (ref "U1") (pin "2") (pinfunction "PD4_2") (pintype "passive"))
    )
    (net (code "62") (name "unconnected-(U1-PD7-Pad11)") (class "Default")
      (node (ref "U1") (pin "11") (pinfunction "PD7_11") (pintype "passive"))
    )
    (net (code "63") (name "unconnected-(U3-ERR-Pad5)") (class "Default")
      (node (ref "U3") (pin "5") (pinfunction "ERR_5") (pintype "passive"))
    )
    (net (code "64") (name "unconnected-(U3-SD-Pad3)") (class "Default")
      (node (ref "U3") (pin "3") (pinfunction "SD_3") (pintype "passive"))
    )
  )
)
